# DAC_adacus_sch.net
KiCad netlist of a schematic drawn in Altium Designer
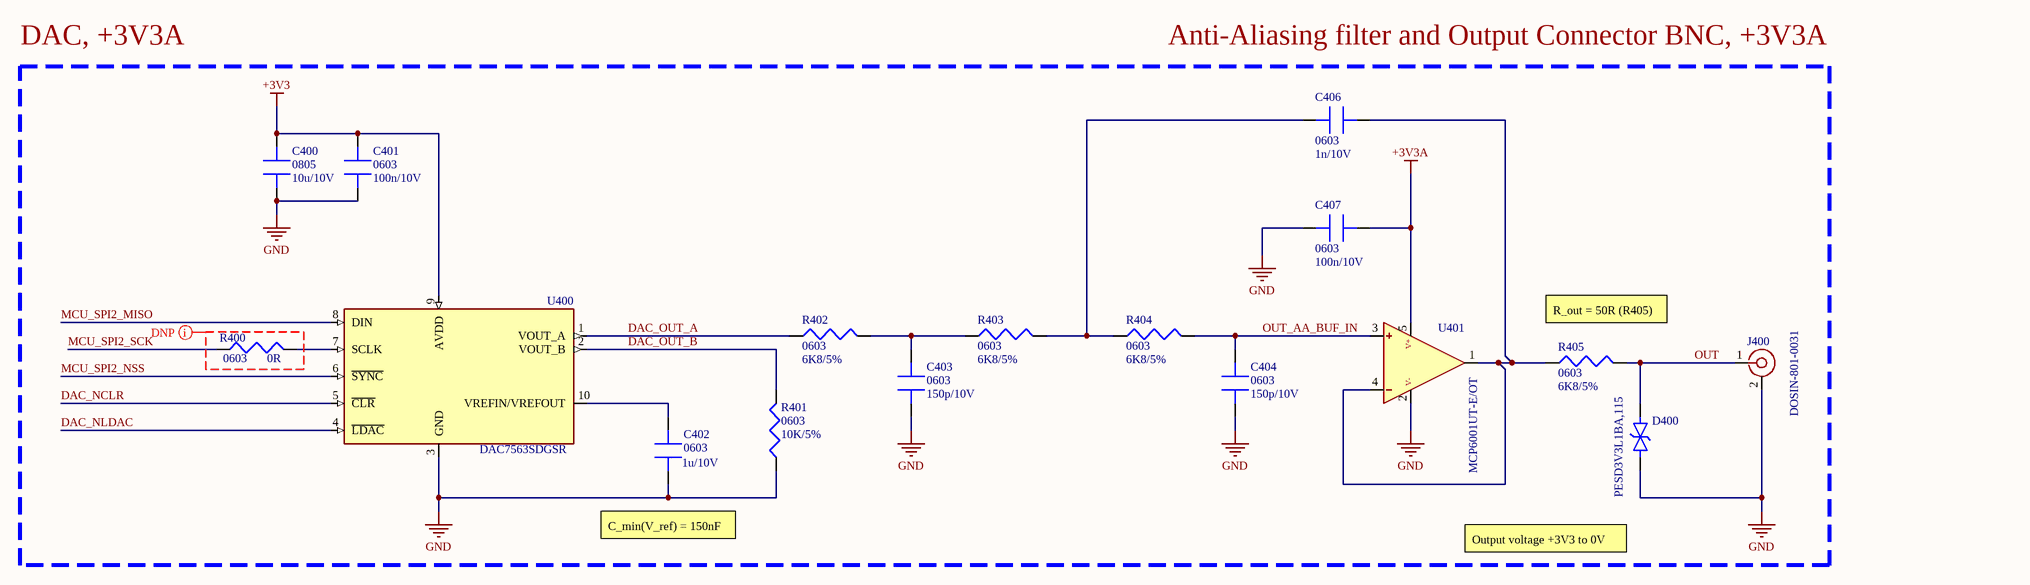
[diagram p0: DAC_adacus_sch.SchDoc]

(export (version "E")
  (design (tool "Eeschema 10.0.6"))
  (components
    (comp (ref "C400")
      (value "10u/10V")
      (footprint "[0805] CAPC2012X09M [A - LD]")
      (description "Standard Capacitor")
      (fields (field (name "PACKAGE") "0805") (field (name "Comment") "Capacitor"))
      (libsource (lib "adacus_schlib") (part "Capacitor"))
    )
    (comp (ref "C401")
      (value "100n/10V")
      (footprint "[0603] CAPC1608X10M [A-LD]")
      (description "Standard Capacitor")
      (fields (field (name "PACKAGE") "0603") (field (name "Comment") "Capacitor"))
      (libsource (lib "adacus_schlib") (part "Capacitor"))
    )
    (comp (ref "C402")
      (value "1u/10V")
      (footprint "[0603] CAPC1608X10M [A-LD]")
      (description "Standard Capacitor")
      (fields (field (name "PACKAGE") "0603") (field (name "Comment") "Capacitor"))
      (libsource (lib "adacus_schlib") (part "Capacitor"))
    )
    (comp (ref "C403")
      (value "150p/10V")
      (footprint "[0603] CAPC1608X10M [A-LD]")
      (description "Standard Capacitor")
      (fields (field (name "PACKAGE") "0603") (field (name "Comment") "Capacitor"))
      (libsource (lib "adacus_schlib") (part "Capacitor"))
    )
    (comp (ref "C404")
      (value "150p/10V")
      (footprint "[0603] CAPC1608X10M [A-LD]")
      (description "Standard Capacitor")
      (fields (field (name "PACKAGE") "0603") (field (name "Comment") "Capacitor"))
      (libsource (lib "adacus_schlib") (part "Capacitor"))
    )
    (comp (ref "C406")
      (value "1n/10V")
      (footprint "[0603] CAPC1608X10M [A-LD]")
      (description "Standard Capacitor")
      (fields (field (name "PACKAGE") "0603") (field (name "Comment") "Capacitor"))
      (libsource (lib "adacus_schlib") (part "Capacitor"))
    )
    (comp (ref "C407")
      (value "100n/10V")
      (footprint "[0603] CAPC1608X10M [A-LD]")
      (description "Standard Capacitor")
      (fields (field (name "PACKAGE") "0603") (field (name "Comment") "Capacitor"))
      (libsource (lib "adacus_schlib") (part "Capacitor"))
    )
    (comp (ref "D400")
      (value "PESD3V3L1BA,115")
      (footprint "SODFL250X110-2M")
      (description "ESD Suppressors / TVS Diodes PESD3V3L1BA/SOD323/SOD2")
      (libsource (lib "adacus_schlib") (part "PESD3V3L1BA,115"))
    )
    (comp (ref "J400")
      (value "DOSIN-801-0031")
      (footprint "DOSIN8010031")
      (description "BNC Board Edge Bend 9.6mm Plugin RF Connectors / Coaxial Connectors")
      (libsource (lib "adacus_schlib") (part "BNC Connector"))
    )
    (comp (ref "R400")
      (value "0R")
      (footprint "[0603] RESC1608X06M [A-LD]")
      (description "Standard Resistor")
      (fields (field (name "PACKAGE") "0603") (field (name "Comment") "Resistor"))
      (libsource (lib "adacus_schlib") (part "Resistor"))
    )
    (comp (ref "R401")
      (value "10K/5%")
      (footprint "[0603] RESC1608X06M [A-LD]")
      (description "Standard Resistor")
      (fields (field (name "PACKAGE") "0603") (field (name "Comment") "Resistor"))
      (libsource (lib "adacus_schlib") (part "Resistor"))
    )
    (comp (ref "R402")
      (value "6K8/5%")
      (footprint "[0603] RESC1608X06M [A-LD]")
      (description "Standard Resistor")
      (fields (field (name "PACKAGE") "0603") (field (name "Comment") "Resistor"))
      (libsource (lib "adacus_schlib") (part "Resistor"))
    )
    (comp (ref "R403")
      (value "6K8/5%")
      (footprint "[0603] RESC1608X06M [A-LD]")
      (description "Standard Resistor")
      (fields (field (name "PACKAGE") "0603") (field (name "Comment") "Resistor"))
      (libsource (lib "adacus_schlib") (part "Resistor"))
    )
    (comp (ref "R404")
      (value "6K8/5%")
      (footprint "[0603] RESC1608X06M [A-LD]")
      (description "Standard Resistor")
      (fields (field (name "PACKAGE") "0603") (field (name "Comment") "Resistor"))
      (libsource (lib "adacus_schlib") (part "Resistor"))
    )
    (comp (ref "R405")
      (value "6K8/5%")
      (footprint "[0603] RESC1608X06M [A-LD]")
      (description "Standard Resistor")
      (fields (field (name "PACKAGE") "0603") (field (name "Comment") "Resistor"))
      (libsource (lib "adacus_schlib") (part "Resistor"))
    )
    (comp (ref "U400")
      (value "DAC7563SDGSR")
      (footprint "TSSOP50P490X110-10M")
      (description "Digital to Analog Converters - DAC 12B,Dual,Lo Pwr Ultra-Lo Glitch DAC")
      (libsource (lib "adacus_schlib") (part "DAC7563SDGSR"))
    )
    (comp (ref "U401")
      (value "MCP6001UT-E/OT")
      (footprint "SOT95P270X145-5M")
      (description "Operational Amplifiers - Op Amps Single 1.8V 1MHz")
      (libsource (lib "adacus_schlib") (part "MCP6001UT-E/OT"))
    )
  )
  (nets
    (net (code "1") (name "+3V3") (class "Default")
      (node (ref "C400") (pin "2") (pinfunction "2_2") (pintype "passive"))
      (node (ref "C401") (pin "2") (pinfunction "2_2") (pintype "passive"))
      (node (ref "U400") (pin "9") (pinfunction "AVDD_9") (pintype "input"))
    )
    (net (code "2") (name "+3V3A") (class "Default")
      (node (ref "C407") (pin "1") (pinfunction "1_1") (pintype "passive"))
      (node (ref "U401") (pin "5") (pinfunction "VDD_5") (pintype "passive"))
    )
    (net (code "3") (name "/DAC_NCLR") (class "Default")
      (node (ref "U400") (pin "5") (pinfunction "~{CLR}_5") (pintype "input"))
    )
    (net (code "4") (name "/DAC_NLDAC") (class "Default")
      (node (ref "U400") (pin "4") (pinfunction "~{LDAC}_4") (pintype "input"))
    )
    (net (code "5") (name "/DAC_OUT_A") (class "Default")
      (node (ref "R402") (pin "2") (pinfunction "2_2") (pintype "passive"))
      (node (ref "U400") (pin "1") (pinfunction "VOUT_A_1") (pintype "output"))
    )
    (net (code "6") (name "/DAC_OUT_B") (class "Default")
      (node (ref "R401") (pin "1") (pinfunction "1_1") (pintype "passive"))
      (node (ref "U400") (pin "2") (pinfunction "VOUT_B_2") (pintype "output"))
    )
    (net (code "7") (name "/MCU_SPI2_MISO") (class "Default")
      (node (ref "U400") (pin "8") (pinfunction "DIN_8") (pintype "input"))
    )
    (net (code "8") (name "/MCU_SPI2_NSS") (class "Default")
      (node (ref "U400") (pin "6") (pinfunction "~{SYNC}_6") (pintype "input"))
    )
    (net (code "9") (name "/MCU_SPI2_SCK") (class "Default")
      (node (ref "R400") (pin "2") (pinfunction "2_2") (pintype "passive"))
    )
    (net (code "10") (name "/OUT") (class "Default")
      (node (ref "D400") (pin "2") (pinfunction "2_2") (pintype "passive"))
      (node (ref "J400") (pin "1") (pinfunction "1_1") (pintype "passive"))
      (node (ref "R405") (pin "1") (pinfunction "1_1") (pintype "passive"))
    )
    (net (code "11") (name "/OUT_AA_BUF_IN") (class "Default")
      (node (ref "C404") (pin "2") (pinfunction "2_2") (pintype "passive"))
      (node (ref "R404") (pin "1") (pinfunction "1_1") (pintype "passive"))
      (node (ref "U401") (pin "3") (pinfunction "+_3") (pintype "passive"))
    )
    (net (code "12") (name "GND") (class "Default")
      (node (ref "C400") (pin "1") (pinfunction "1_1") (pintype "passive"))
      (node (ref "C401") (pin "1") (pinfunction "1_1") (pintype "passive"))
      (node (ref "C402") (pin "1") (pinfunction "1_1") (pintype "passive"))
      (node (ref "C403") (pin "1") (pinfunction "1_1") (pintype "passive"))
      (node (ref "C404") (pin "1") (pinfunction "1_1") (pintype "passive"))
      (node (ref "C407") (pin "2") (pinfunction "2_2") (pintype "passive"))
      (node (ref "D400") (pin "1") (pinfunction "1_1") (pintype "passive"))
      (node (ref "J400") (pin "2") (pinfunction "2_2") (pintype "passive"))
      (node (ref "R401") (pin "2") (pinfunction "2_2") (pintype "passive"))
      (node (ref "U400") (pin "3") (pinfunction "GND_3") (pintype "passive"))
      (node (ref "U401") (pin "2") (pinfunction "VSS_2") (pintype "passive"))
    )
    (net (code "13") (name "Net-(C403-Pad2)") (class "Default")
      (node (ref "C403") (pin "2") (pinfunction "2_2") (pintype "passive"))
      (node (ref "R402") (pin "1") (pinfunction "1_1") (pintype "passive"))
      (node (ref "R403") (pin "2") (pinfunction "2_2") (pintype "passive"))
    )
    (net (code "14") (name "Net-(C406-Pad2)") (class "Default")
      (node (ref "C406") (pin "2") (pinfunction "2_2") (pintype "passive"))
      (node (ref "R403") (pin "1") (pinfunction "1_1") (pintype "passive"))
      (node (ref "R404") (pin "2") (pinfunction "2_2") (pintype "passive"))
    )
    (net (code "15") (name "Net-(U400-SCLK)") (class "Default")
      (node (ref "R400") (pin "1") (pinfunction "1_1") (pintype "passive"))
      (node (ref "U400") (pin "7") (pinfunction "SCLK_7") (pintype "input"))
    )
    (net (code "16") (name "Net-(U400-VREFIN{slash}VREFOUT)") (class "Default")
      (node (ref "C402") (pin "2") (pinfunction "2_2") (pintype "passive"))
      (node (ref "U400") (pin "10") (pinfunction "VREFIN/VREFOUT_10") (pintype "bidirectional"))
    )
    (net (code "17") (name "Net-(U401--)") (class "Default")
      (node (ref "C406") (pin "1") (pinfunction "1_1") (pintype "passive"))
      (node (ref "R405") (pin "2") (pinfunction "2_2") (pintype "passive"))
      (node (ref "U401") (pin "1") (pinfunction "OUT_1") (pintype "passive"))
      (node (ref "U401") (pin "4") (pinfunction "-_4") (pintype "passive"))
    )
  )
)
